# Sheet1_TLK.net
KiCad netlist of a schematic drawn in Altium Designer
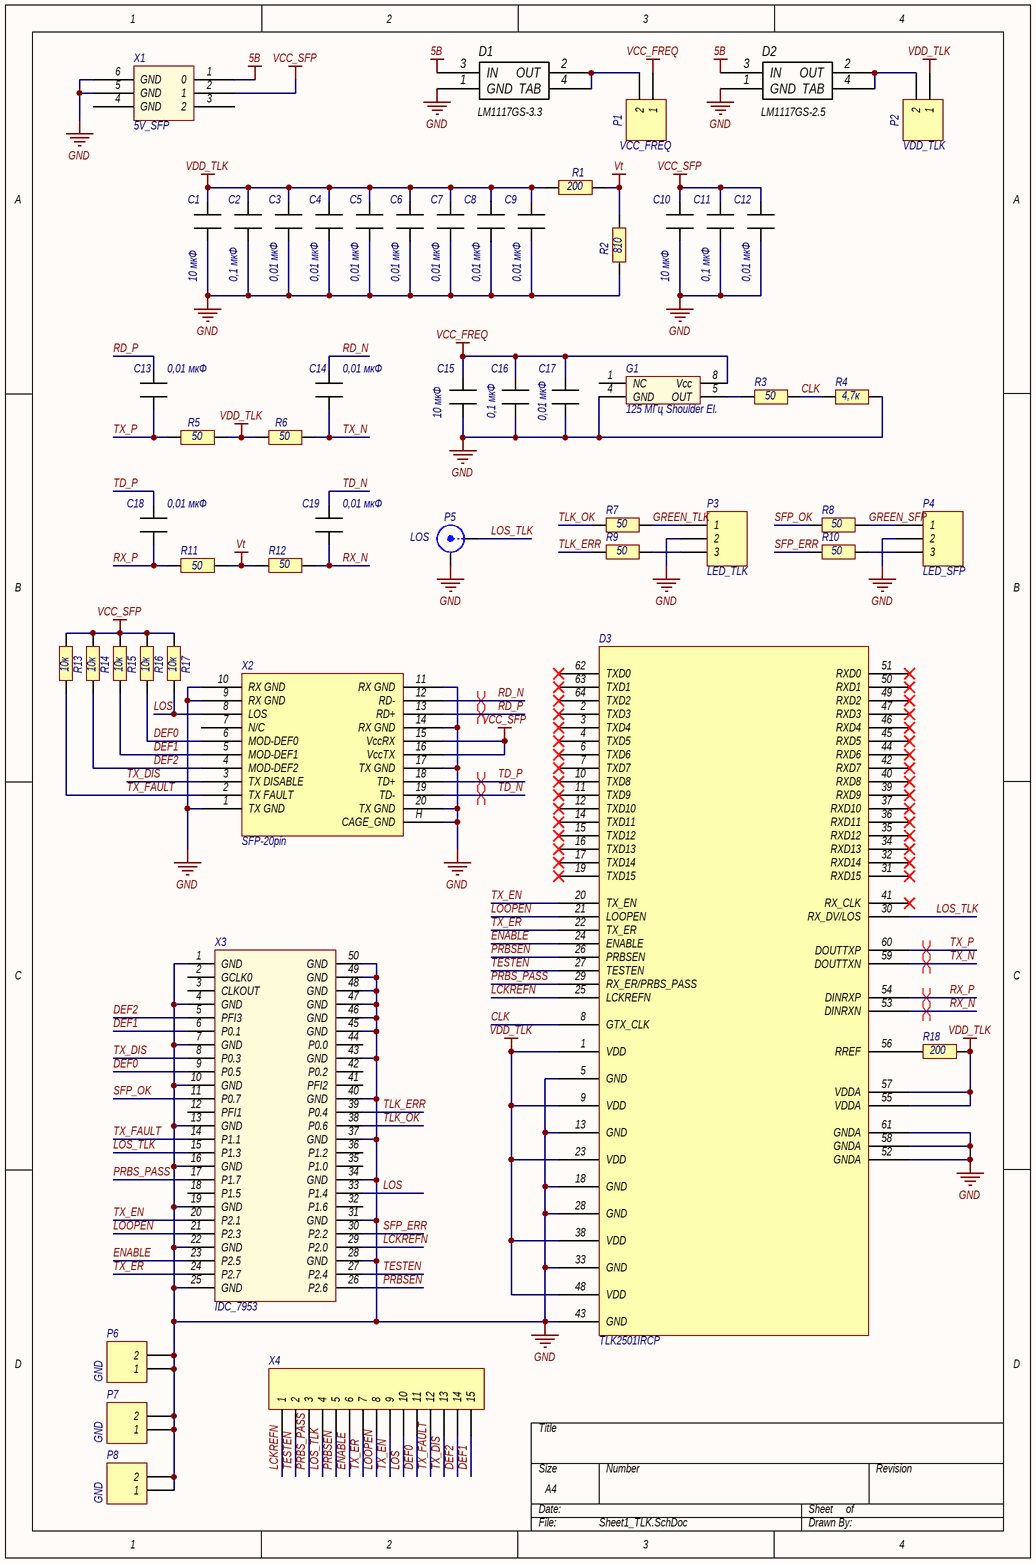
[diagram p0: Sheet1_TLK.SchDoc]

(export (version "E")
  (design (tool "Eeschema 10.0.6"))
  (components
    (comp (ref "C1") (value "10 мкФ") (footprint "Cap_BIG") (libsource (lib "Schlib") (part "CAP_BIG")))
    (comp (ref "C2") (value "0,1 мкФ") (footprint "CAP_SMALL") (libsource (lib "Schlib") (part "CAP_SMALL")))
    (comp (ref "C3") (value "0,01 мкФ") (footprint "CAP_SMALL") (libsource (lib "Schlib") (part "CAP_SMALL")))
    (comp (ref "C4") (value "0,01 мкФ") (footprint "CAP_SMALL") (libsource (lib "Schlib") (part "CAP_SMALL")))
    (comp (ref "C5") (value "0,01 мкФ") (footprint "CAP_SMALL") (libsource (lib "Schlib") (part "CAP_SMALL")))
    (comp (ref "C6") (value "0,01 мкФ") (footprint "CAP_SMALL") (libsource (lib "Schlib") (part "CAP_SMALL")))
    (comp (ref "C7") (value "0,01 мкФ") (footprint "CAP_SMALL") (libsource (lib "Schlib") (part "CAP_SMALL")))
    (comp (ref "C8") (value "0,01 мкФ") (footprint "CAP_SMALL") (libsource (lib "Schlib") (part "CAP_SMALL")))
    (comp (ref "C9") (value "0,01 мкФ") (footprint "CAP_SMALL") (libsource (lib "Schlib") (part "CAP_SMALL")))
    (comp (ref "C10") (value "10 мкФ") (footprint "Cap_BIG") (libsource (lib "Schlib") (part "CAP_BIG")))
    (comp (ref "C11") (value "0,1 мкФ") (footprint "CAP_SMALL") (libsource (lib "Schlib") (part "CAP_SMALL")))
    (comp (ref "C12")
      (value "0,01 мкФ")
      (footprint "CAP_SMALL")
      (libsource (lib "Schlib") (part "CAP_SMALL"))
    )
    (comp (ref "C13")
      (value "0,01 мкФ")
      (footprint "CAP_SMALL")
      (libsource (lib "Schlib") (part "CAP_SMALL"))
    )
    (comp (ref "C14")
      (value "0,01 мкФ")
      (footprint "CAP_SMALL")
      (libsource (lib "Schlib") (part "CAP_SMALL"))
    )
    (comp (ref "C15") (value "10 мкФ") (footprint "Cap_BIG") (libsource (lib "Schlib") (part "CAP_BIG")))
    (comp (ref "C16") (value "0,1 мкФ") (footprint "CAP_SMALL") (libsource (lib "Schlib") (part "CAP_SMALL")))
    (comp (ref "C17")
      (value "0,01 мкФ")
      (footprint "CAP_SMALL")
      (libsource (lib "Schlib") (part "CAP_SMALL"))
    )
    (comp (ref "C18")
      (value "0,01 мкФ")
      (footprint "CAP_SMALL")
      (libsource (lib "Schlib") (part "CAP_SMALL"))
    )
    (comp (ref "C19")
      (value "0,01 мкФ")
      (footprint "CAP_SMALL")
      (libsource (lib "Schlib") (part "CAP_SMALL"))
    )
    (comp (ref "D1")
      (value "LM1117GS-3.3")
      (footprint "LM1117_SOT223")
      (description "Стабилизатор напряжения 3,3В")
      (libsource (lib "VPL") (part "LM1117GS-3.3"))
    )
    (comp (ref "D2")
      (value "LM1117GS-2.5")
      (footprint "LM1117_SOT223")
      (description "Стабилизатор напряжения 2,5В")
      (libsource (lib "VPL") (part "LM1117GS-2.5"))
    )
    (comp (ref "D3")
      (value "TLK2501IRCP")
      (footprint "Quad64")
      (libsource (lib "MIT_Schlib") (part "TLK2501IRCP"))
    )
    (comp (ref "G1")
      (value "125 МГц Shoulder El.")
      (footprint "HALF")
      (libsource (lib "VPL") (part "125 МГц Shoulder El."))
    )
    (comp (ref "P1")
      (value "VCC_FREQ")
      (footprint "HDR1X2")
      (description "Header, 2-Pin")
      (fields (field (name "PUBLISHER") "Altium Limited"))
      (libsource (lib "Miscellaneous Connectors") (part "Header 2"))
    )
    (comp (ref "P2")
      (value "VDD_TLK")
      (footprint "HDR1X2")
      (description "Header, 2-Pin")
      (fields (field (name "PUBLISHER") "Altium Limited"))
      (libsource (lib "Miscellaneous Connectors") (part "Header 2"))
    )
    (comp (ref "P3")
      (value "LED_TLK")
      (footprint "HDR1X3")
      (description "Header, 3-Pin")
      (fields (field (name "PUBLISHER") "Altium Limited"))
      (libsource (lib "Miscellaneous Connectors") (part "Header 3"))
    )
    (comp (ref "P4")
      (value "LED_SFP")
      (footprint "HDR1X3")
      (description "Header, 3-Pin")
      (fields (field (name "PUBLISHER") "Altium Limited"))
      (libsource (lib "Miscellaneous Connectors") (part "Header 3"))
    )
    (comp (ref "P5")
      (value "LOS")
      (footprint "BNC_RA CON")
      (description "BNC Elbow Connector")
      (fields (field (name "PUBLISHER") "Altium Limited"))
      (libsource (lib "Miscellaneous Connectors") (part "BNC"))
    )
    (comp (ref "P6")
      (value "GND")
      (footprint "HDR1X2")
      (description "Header, 2-Pin")
      (fields (field (name "PUBLISHER") "Altium Limited"))
      (libsource (lib "") (part "Header 2_1"))
    )
    (comp (ref "P7")
      (value "GND")
      (footprint "HDR1X2")
      (description "Header, 2-Pin")
      (fields (field (name "PUBLISHER") "Altium Limited"))
      (libsource (lib "") (part "Header 2_1"))
    )
    (comp (ref "P8")
      (value "GND")
      (footprint "HDR1X2")
      (description "Header, 2-Pin")
      (fields (field (name "PUBLISHER") "Altium Limited"))
      (libsource (lib "") (part "Header 2_1"))
    )
    (comp (ref "R1") (value "200") (footprint "RES") (libsource (lib "") (part "RES_2")))
    (comp (ref "R2") (value "810") (footprint "RES") (libsource (lib "") (part "RES_1")))
    (comp (ref "R3") (value "50") (footprint "RES") (libsource (lib "Schlib") (part "RES")))
    (comp (ref "R4") (value "4,7к") (footprint "RES") (libsource (lib "Schlib") (part "RES")))
    (comp (ref "R5") (value "50") (footprint "RES") (libsource (lib "Schlib") (part "RES")))
    (comp (ref "R6") (value "50") (footprint "RES") (libsource (lib "Schlib") (part "RES")))
    (comp (ref "R7") (value "50") (footprint "RES") (libsource (lib "Schlib") (part "RES")))
    (comp (ref "R8") (value "50") (footprint "RES") (libsource (lib "Schlib") (part "RES")))
    (comp (ref "R9") (value "50") (footprint "RES") (libsource (lib "Schlib") (part "RES")))
    (comp (ref "R10") (value "50") (footprint "RES") (libsource (lib "Schlib") (part "RES")))
    (comp (ref "R11") (value "50") (footprint "RES") (libsource (lib "Schlib") (part "RES")))
    (comp (ref "R12") (value "50") (footprint "RES") (libsource (lib "Schlib") (part "RES")))
    (comp (ref "R13") (value "10к") (footprint "RES") (libsource (lib "") (part "RES_1")))
    (comp (ref "R14") (value "10к") (footprint "RES") (libsource (lib "") (part "RES_1")))
    (comp (ref "R15") (value "10к") (footprint "RES") (libsource (lib "") (part "RES_1")))
    (comp (ref "R16") (value "10к") (footprint "RES") (libsource (lib "") (part "RES_1")))
    (comp (ref "R17") (value "10к") (footprint "RES") (libsource (lib "") (part "RES_1")))
    (comp (ref "R18") (value "200") (footprint "RES") (libsource (lib "Schlib") (part "RES")))
    (comp (ref "X1") (value "5V_SFP") (footprint "POWER") (libsource (lib "Schlib") (part "POWER")))
    (comp (ref "X2")
      (value "SFP-20pin")
      (footprint "SFP-20pin")
      (libsource (lib "MIT_Schlib") (part "SFP-20pin"))
    )
    (comp (ref "X3") (value "IDC_7953") (footprint "IDC_7953") (libsource (lib "VPL") (part "IDC_7953")))
    (comp (ref "X4")
      (value "Header 15")
      (footprint "HDR1X15")
      (description "Header, 15-Pin")
      (fields (field (name "PUBLISHER") "Altium Limited"))
      (libsource (lib "Miscellaneous Connectors") (part "Header 15"))
    )
  )
  (nets
    (net (code "1") (name "/CLK") (class "Default")
      (node (ref "D3") (pin "8") (pinfunction "GTX_CLK_8") (pintype "passive"))
      (node (ref "R3") (pin "2") (pinfunction "2_2") (pintype "passive"))
      (node (ref "R4") (pin "1") (pinfunction "1_1") (pintype "passive"))
    )
    (net (code "2") (name "/DEF0") (class "Default")
      (node (ref "R16") (pin "1") (pinfunction "1_1") (pintype "passive"))
      (node (ref "X2") (pin "6") (pinfunction "MOD-DEF0_6") (pintype "passive"))
      (node (ref "X3") (pin "9") (pinfunction "P0.5_9") (pintype "passive"))
      (node (ref "X4") (pin "11") (pinfunction "11_11") (pintype "passive"))
    )
    (net (code "3") (name "/DEF1") (class "Default")
      (node (ref "R15") (pin "1") (pinfunction "1_1") (pintype "passive"))
      (node (ref "X2") (pin "5") (pinfunction "MOD-DEF1_5") (pintype "passive"))
      (node (ref "X3") (pin "6") (pinfunction "P0.1_6") (pintype "passive"))
      (node (ref "X4") (pin "15") (pinfunction "15_15") (pintype "passive"))
    )
    (net (code "4") (name "/DEF2") (class "Default")
      (node (ref "R14") (pin "1") (pinfunction "1_1") (pintype "passive"))
      (node (ref "X2") (pin "4") (pinfunction "MOD-DEF2_4") (pintype "passive"))
      (node (ref "X3") (pin "5") (pinfunction "PFI3_5") (pintype "passive"))
      (node (ref "X4") (pin "14") (pinfunction "14_14") (pintype "passive"))
    )
    (net (code "5") (name "/ENABLE") (class "Default")
      (node (ref "D3") (pin "24") (pinfunction "ENABLE_24") (pintype "passive"))
      (node (ref "X3") (pin "23") (pinfunction "P2.5_23") (pintype "passive"))
      (node (ref "X4") (pin "6") (pinfunction "6_6") (pintype "passive"))
    )
    (net (code "6") (name "/GREEN_SFP") (class "Default")
      (node (ref "P4") (pin "1") (pinfunction "1_1") (pintype "passive"))
      (node (ref "R8") (pin "2") (pinfunction "2_2") (pintype "passive"))
    )
    (net (code "7") (name "/GREEN_TLK") (class "Default")
      (node (ref "P3") (pin "1") (pinfunction "1_1") (pintype "passive"))
      (node (ref "R7") (pin "2") (pinfunction "2_2") (pintype "passive"))
    )
    (net (code "8") (name "/LCKREFN") (class "Default")
      (node (ref "D3") (pin "25") (pinfunction "LCKREFN_25") (pintype "passive"))
      (node (ref "X3") (pin "29") (pinfunction "P2.0_29") (pintype "passive"))
      (node (ref "X4") (pin "1") (pinfunction "1_1") (pintype "passive"))
    )
    (net (code "9") (name "/LOOPEN") (class "Default")
      (node (ref "D3") (pin "21") (pinfunction "LOOPEN_21") (pintype "passive"))
      (node (ref "X3") (pin "21") (pinfunction "P2.3_21") (pintype "passive"))
      (node (ref "X4") (pin "8") (pinfunction "8_8") (pintype "passive"))
    )
    (net (code "10") (name "/LOS") (class "Default")
      (node (ref "R17") (pin "1") (pinfunction "1_1") (pintype "passive"))
      (node (ref "X2") (pin "8") (pinfunction "LOS_8") (pintype "passive"))
      (node (ref "X3") (pin "33") (pinfunction "P1.4_33") (pintype "passive"))
      (node (ref "X4") (pin "10") (pinfunction "10_10") (pintype "passive"))
    )
    (net (code "11") (name "/LOS_TLK") (class "Default")
      (node (ref "D3") (pin "30") (pinfunction "RX_DV/LOS_30") (pintype "passive"))
      (node (ref "P5") (pin "1") (pinfunction "X_1") (pintype "passive"))
      (node (ref "X3") (pin "15") (pinfunction "P1.3_15") (pintype "passive"))
      (node (ref "X4") (pin "4") (pinfunction "4_4") (pintype "passive"))
    )
    (net (code "12") (name "/PRBSEN") (class "Default")
      (node (ref "D3") (pin "26") (pinfunction "PRBSEN_26") (pintype "passive"))
      (node (ref "X3") (pin "26") (pinfunction "P2.6_26") (pintype "passive"))
      (node (ref "X4") (pin "5") (pinfunction "5_5") (pintype "passive"))
    )
    (net (code "13") (name "/PRBS_PASS") (class "Default")
      (node (ref "D3") (pin "29") (pinfunction "RX_ER/PRBS_PASS_29") (pintype "passive"))
      (node (ref "X3") (pin "17") (pinfunction "P1.7_17") (pintype "passive"))
      (node (ref "X4") (pin "3") (pinfunction "3_3") (pintype "passive"))
    )
    (net (code "14") (name "/RD_N") (class "Default")
      (node (ref "C14") (pin "2") (pinfunction "2_2") (pintype "passive"))
      (node (ref "X2") (pin "12") (pinfunction "RD-_12") (pintype "passive"))
    )
    (net (code "15") (name "/RD_P") (class "Default")
      (node (ref "C13") (pin "2") (pinfunction "2_2") (pintype "passive"))
      (node (ref "X2") (pin "13") (pinfunction "RD+_13") (pintype "passive"))
    )
    (net (code "16") (name "/RX_N") (class "Default")
      (node (ref "C19") (pin "1") (pinfunction "1_1") (pintype "passive"))
      (node (ref "D3") (pin "53") (pinfunction "DINRXN_53") (pintype "passive"))
      (node (ref "R12") (pin "2") (pinfunction "2_2") (pintype "passive"))
    )
    (net (code "17") (name "/RX_P") (class "Default")
      (node (ref "C18") (pin "1") (pinfunction "1_1") (pintype "passive"))
      (node (ref "D3") (pin "54") (pinfunction "DINRXP_54") (pintype "passive"))
      (node (ref "R11") (pin "1") (pinfunction "1_1") (pintype "passive"))
    )
    (net (code "18") (name "/SFP_ERR") (class "Default")
      (node (ref "R10") (pin "1") (pinfunction "1_1") (pintype "passive"))
      (node (ref "X3") (pin "30") (pinfunction "P2.2_30") (pintype "passive"))
    )
    (net (code "19") (name "/SFP_OK") (class "Default")
      (node (ref "R8") (pin "1") (pinfunction "1_1") (pintype "passive"))
      (node (ref "X3") (pin "11") (pinfunction "P0.7_11") (pintype "passive"))
    )
    (net (code "20") (name "/TD_N") (class "Default")
      (node (ref "C19") (pin "2") (pinfunction "2_2") (pintype "passive"))
      (node (ref "X2") (pin "19") (pinfunction "TD-_19") (pintype "passive"))
    )
    (net (code "21") (name "/TD_P") (class "Default")
      (node (ref "C18") (pin "2") (pinfunction "2_2") (pintype "passive"))
      (node (ref "X2") (pin "18") (pinfunction "TD+_18") (pintype "passive"))
    )
    (net (code "22") (name "/TESTEN") (class "Default")
      (node (ref "D3") (pin "27") (pinfunction "TESTEN_27") (pintype "passive"))
      (node (ref "X3") (pin "27") (pinfunction "P2.4_27") (pintype "passive"))
      (node (ref "X4") (pin "2") (pinfunction "2_2") (pintype "passive"))
    )
    (net (code "23") (name "/TLK_ERR") (class "Default")
      (node (ref "R9") (pin "1") (pinfunction "1_1") (pintype "passive"))
      (node (ref "X3") (pin "39") (pinfunction "P0.4_39") (pintype "passive"))
    )
    (net (code "24") (name "/TLK_OK") (class "Default")
      (node (ref "R7") (pin "1") (pinfunction "1_1") (pintype "passive"))
      (node (ref "X3") (pin "38") (pinfunction "P0.6_38") (pintype "passive"))
    )
    (net (code "25") (name "/TX_DIS") (class "Default")
      (node (ref "X2") (pin "3") (pinfunction "TX_DISABLE_3") (pintype "passive"))
      (node (ref "X3") (pin "8") (pinfunction "P0.3_8") (pintype "passive"))
      (node (ref "X4") (pin "13") (pinfunction "13_13") (pintype "passive"))
    )
    (net (code "26") (name "/TX_EN") (class "Default")
      (node (ref "D3") (pin "20") (pinfunction "TX_EN_20") (pintype "passive"))
      (node (ref "X3") (pin "20") (pinfunction "P2.1_20") (pintype "passive"))
      (node (ref "X4") (pin "9") (pinfunction "9_9") (pintype "passive"))
    )
    (net (code "27") (name "/TX_ER") (class "Default")
      (node (ref "D3") (pin "22") (pinfunction "TX_ER_22") (pintype "passive"))
      (node (ref "X3") (pin "24") (pinfunction "P2.7_24") (pintype "passive"))
      (node (ref "X4") (pin "7") (pinfunction "7_7") (pintype "passive"))
    )
    (net (code "28") (name "/TX_FAULT") (class "Default")
      (node (ref "R13") (pin "1") (pinfunction "1_1") (pintype "passive"))
      (node (ref "X2") (pin "2") (pinfunction "TX_FAULT_2") (pintype "passive"))
      (node (ref "X3") (pin "14") (pinfunction "P1.1_14") (pintype "passive"))
      (node (ref "X4") (pin "12") (pinfunction "12_12") (pintype "passive"))
    )
    (net (code "29") (name "/TX_N") (class "Default")
      (node (ref "C14") (pin "1") (pinfunction "1_1") (pintype "passive"))
      (node (ref "D3") (pin "59") (pinfunction "DOUTTXN_59") (pintype "passive"))
      (node (ref "R6") (pin "2") (pinfunction "2_2") (pintype "passive"))
    )
    (net (code "30") (name "/TX_P") (class "Default")
      (node (ref "C13") (pin "1") (pinfunction "1_1") (pintype "passive"))
      (node (ref "D3") (pin "60") (pinfunction "DOUTTXP_60") (pintype "passive"))
      (node (ref "R5") (pin "1") (pinfunction "1_1") (pintype "passive"))
    )
    (net (code "31") (name "5В") (class "Default")
      (node (ref "D1") (pin "3") (pinfunction "IN_3") (pintype "power_in"))
      (node (ref "D2") (pin "3") (pinfunction "IN_3") (pintype "power_in"))
      (node (ref "X1") (pin "1") (pinfunction "0_1") (pintype "passive"))
    )
    (net (code "32") (name "GND") (class "Default")
      (node (ref "C1") (pin "1") (pinfunction "1_1") (pintype "passive"))
      (node (ref "C10") (pin "1") (pinfunction "1_1") (pintype "passive"))
      (node (ref "C11") (pin "1") (pinfunction "1_1") (pintype "passive"))
      (node (ref "C12") (pin "1") (pinfunction "1_1") (pintype "passive"))
      (node (ref "C15") (pin "1") (pinfunction "1_1") (pintype "passive"))
      (node (ref "C16") (pin "1") (pinfunction "1_1") (pintype "passive"))
      (node (ref "C17") (pin "1") (pinfunction "1_1") (pintype "passive"))
      (node (ref "C2") (pin "1") (pinfunction "1_1") (pintype "passive"))
      (node (ref "C3") (pin "1") (pinfunction "1_1") (pintype "passive"))
      (node (ref "C4") (pin "1") (pinfunction "1_1") (pintype "passive"))
      (node (ref "C5") (pin "1") (pinfunction "1_1") (pintype "passive"))
      (node (ref "C6") (pin "1") (pinfunction "1_1") (pintype "passive"))
      (node (ref "C7") (pin "1") (pinfunction "1_1") (pintype "passive"))
      (node (ref "C8") (pin "1") (pinfunction "1_1") (pintype "passive"))
      (node (ref "C9") (pin "1") (pinfunction "1_1") (pintype "passive"))
      (node (ref "D1") (pin "1") (pinfunction "GND_1") (pintype "passive"))
      (node (ref "D2") (pin "1") (pinfunction "GND_1") (pintype "passive"))
      (node (ref "D3") (pin "13") (pinfunction "GND_13") (pintype "passive"))
      (node (ref "D3") (pin "18") (pinfunction "GND_18") (pintype "passive"))
      (node (ref "D3") (pin "28") (pinfunction "GND_28") (pintype "passive"))
      (node (ref "D3") (pin "33") (pinfunction "GND_33") (pintype "passive"))
      (node (ref "D3") (pin "43") (pinfunction "GND_43") (pintype "passive"))
      (node (ref "D3") (pin "5") (pinfunction "GND_5") (pintype "passive"))
      (node (ref "D3") (pin "52") (pinfunction "GNDA_52") (pintype "passive"))
      (node (ref "D3") (pin "58") (pinfunction "GNDA_58") (pintype "passive"))
      (node (ref "D3") (pin "61") (pinfunction "GNDA_61") (pintype "passive"))
      (node (ref "G1") (pin "4") (pinfunction "GND_4") (pintype "passive"))
      (node (ref "P3") (pin "2") (pinfunction "2_2") (pintype "passive"))
      (node (ref "P4") (pin "2") (pinfunction "2_2") (pintype "passive"))
      (node (ref "P5") (pin "2") (pinfunction "Y_2") (pintype "passive"))
      (node (ref "P6") (pin "1") (pinfunction "1_1") (pintype "passive"))
      (node (ref "P6") (pin "2") (pinfunction "2_2") (pintype "passive"))
      (node (ref "P7") (pin "1") (pinfunction "1_1") (pintype "passive"))
      (node (ref "P7") (pin "2") (pinfunction "2_2") (pintype "passive"))
      (node (ref "P8") (pin "1") (pinfunction "1_1") (pintype "passive"))
      (node (ref "P8") (pin "2") (pinfunction "2_2") (pintype "passive"))
      (node (ref "R2") (pin "1") (pinfunction "1_1") (pintype "passive"))
      (node (ref "R4") (pin "2") (pinfunction "2_2") (pintype "passive"))
      (node (ref "X1") (pin "5") (pinfunction "GND_5") (pintype "passive"))
      (node (ref "X1") (pin "6") (pinfunction "GND_6") (pintype "passive"))
      (node (ref "X2") (pin "1") (pinfunction "TX_GND_1") (pintype "passive"))
      (node (ref "X2") (pin "10") (pinfunction "RX_GND_10") (pintype "passive"))
      (node (ref "X2") (pin "11") (pinfunction "RX_GND_11") (pintype "passive"))
      (node (ref "X2") (pin "14") (pinfunction "RX_GND_14") (pintype "passive"))
      (node (ref "X2") (pin "17") (pinfunction "TX_GND_17") (pintype "passive"))
      (node (ref "X2") (pin "20") (pinfunction "TX_GND_20") (pintype "passive"))
      (node (ref "X2") (pin "9") (pinfunction "RX_GND_9") (pintype "passive"))
      (node (ref "X2") (pin "H") (pinfunction "CAGE_GND_H") (pintype "passive"))
      (node (ref "X3") (pin "1") (pinfunction "GND_1") (pintype "passive"))
      (node (ref "X3") (pin "10") (pinfunction "GND_10") (pintype "passive"))
      (node (ref "X3") (pin "13") (pinfunction "GND_13") (pintype "passive"))
      (node (ref "X3") (pin "16") (pinfunction "GND_16") (pintype "passive"))
      (node (ref "X3") (pin "19") (pinfunction "GND_19") (pintype "passive"))
      (node (ref "X3") (pin "22") (pinfunction "GND_22") (pintype "passive"))
      (node (ref "X3") (pin "25") (pinfunction "GND_25") (pintype "passive"))
      (node (ref "X3") (pin "28") (pinfunction "GND_28") (pintype "passive"))
      (node (ref "X3") (pin "31") (pinfunction "GND_31") (pintype "passive"))
      (node (ref "X3") (pin "34") (pinfunction "GND_34") (pintype "passive"))
      (node (ref "X3") (pin "37") (pinfunction "GND_37") (pintype "passive"))
      (node (ref "X3") (pin "4") (pinfunction "GND_4") (pintype "passive"))
      (node (ref "X3") (pin "40") (pinfunction "GND_40") (pintype "passive"))
      (node (ref "X3") (pin "43") (pinfunction "GND_43") (pintype "passive"))
      (node (ref "X3") (pin "45") (pinfunction "GND_45") (pintype "passive"))
      (node (ref "X3") (pin "46") (pinfunction "GND_46") (pintype "passive"))
      (node (ref "X3") (pin "47") (pinfunction "GND_47") (pintype "passive"))
      (node (ref "X3") (pin "48") (pinfunction "GND_48") (pintype "passive"))
      (node (ref "X3") (pin "49") (pinfunction "GND_49") (pintype "passive"))
      (node (ref "X3") (pin "50") (pinfunction "GND_50") (pintype "passive"))
      (node (ref "X3") (pin "7") (pinfunction "GND_7") (pintype "passive"))
    )
    (net (code "33") (name "Net-(D1-OUT)") (class "Default")
      (node (ref "D1") (pin "2") (pinfunction "OUT_2") (pintype "passive"))
      (node (ref "D1") (pin "4") (pinfunction "TAB_4") (pintype "passive"))
      (node (ref "P1") (pin "2") (pinfunction "2_2") (pintype "passive"))
    )
    (net (code "34") (name "Net-(D2-OUT)") (class "Default")
      (node (ref "D2") (pin "2") (pinfunction "OUT_2") (pintype "passive"))
      (node (ref "D2") (pin "4") (pinfunction "TAB_4") (pintype "passive"))
      (node (ref "P2") (pin "2") (pinfunction "2_2") (pintype "passive"))
    )
    (net (code "35") (name "Net-(D3-RREF)") (class "Default")
      (node (ref "D3") (pin "56") (pinfunction "RREF_56") (pintype "passive"))
      (node (ref "R18") (pin "1") (pinfunction "1_1") (pintype "passive"))
    )
    (net (code "36") (name "Net-(G1-OUT)") (class "Default")
      (node (ref "G1") (pin "5") (pinfunction "OUT_5") (pintype "passive"))
      (node (ref "R3") (pin "1") (pinfunction "1_1") (pintype "passive"))
    )
    (net (code "37") (name "Net-(P3-Pad3)") (class "Default")
      (node (ref "P3") (pin "3") (pinfunction "3_3") (pintype "passive"))
      (node (ref "R9") (pin "2") (pinfunction "2_2") (pintype "passive"))
    )
    (net (code "38") (name "Net-(P4-Pad3)") (class "Default")
      (node (ref "P4") (pin "3") (pinfunction "3_3") (pintype "passive"))
      (node (ref "R10") (pin "2") (pinfunction "2_2") (pintype "passive"))
    )
    (net (code "39") (name "VCC_FREQ") (class "Default")
      (node (ref "C15") (pin "2") (pinfunction "2_2") (pintype "passive"))
      (node (ref "C16") (pin "2") (pinfunction "2_2") (pintype "passive"))
      (node (ref "C17") (pin "2") (pinfunction "2_2") (pintype "passive"))
      (node (ref "G1") (pin "8") (pinfunction "Vcc_8") (pintype "passive"))
      (node (ref "P1") (pin "1") (pinfunction "1_1") (pintype "passive"))
    )
    (net (code "40") (name "VCC_SFP") (class "Default")
      (node (ref "C10") (pin "2") (pinfunction "2_2") (pintype "passive"))
      (node (ref "C11") (pin "2") (pinfunction "2_2") (pintype "passive"))
      (node (ref "C12") (pin "2") (pinfunction "2_2") (pintype "passive"))
      (node (ref "R13") (pin "2") (pinfunction "2_2") (pintype "passive"))
      (node (ref "R14") (pin "2") (pinfunction "2_2") (pintype "passive"))
      (node (ref "R15") (pin "2") (pinfunction "2_2") (pintype "passive"))
      (node (ref "R16") (pin "2") (pinfunction "2_2") (pintype "passive"))
      (node (ref "R17") (pin "2") (pinfunction "2_2") (pintype "passive"))
      (node (ref "X1") (pin "2") (pinfunction "1_2") (pintype "passive"))
      (node (ref "X2") (pin "15") (pinfunction "VccRX_15") (pintype "passive"))
      (node (ref "X2") (pin "16") (pinfunction "VccTX_16") (pintype "passive"))
    )
    (net (code "41") (name "VDD_TLK") (class "Default")
      (node (ref "C1") (pin "2") (pinfunction "2_2") (pintype "passive"))
      (node (ref "C2") (pin "2") (pinfunction "2_2") (pintype "passive"))
      (node (ref "C3") (pin "2") (pinfunction "2_2") (pintype "passive"))
      (node (ref "C4") (pin "2") (pinfunction "2_2") (pintype "passive"))
      (node (ref "C5") (pin "2") (pinfunction "2_2") (pintype "passive"))
      (node (ref "C6") (pin "2") (pinfunction "2_2") (pintype "passive"))
      (node (ref "C7") (pin "2") (pinfunction "2_2") (pintype "passive"))
      (node (ref "C8") (pin "2") (pinfunction "2_2") (pintype "passive"))
      (node (ref "C9") (pin "2") (pinfunction "2_2") (pintype "passive"))
      (node (ref "D3") (pin "1") (pinfunction "VDD_1") (pintype "passive"))
      (node (ref "D3") (pin "23") (pinfunction "VDD_23") (pintype "passive"))
      (node (ref "D3") (pin "38") (pinfunction "VDD_38") (pintype "passive"))
      (node (ref "D3") (pin "48") (pinfunction "VDD_48") (pintype "passive"))
      (node (ref "D3") (pin "55") (pinfunction "VDDA_55") (pintype "passive"))
      (node (ref "D3") (pin "57") (pinfunction "VDDA_57") (pintype "passive"))
      (node (ref "D3") (pin "9") (pinfunction "VDD_9") (pintype "passive"))
      (node (ref "P2") (pin "1") (pinfunction "1_1") (pintype "passive"))
      (node (ref "R1") (pin "2") (pinfunction "2_2") (pintype "passive"))
      (node (ref "R18") (pin "2") (pinfunction "2_2") (pintype "passive"))
      (node (ref "R5") (pin "2") (pinfunction "2_2") (pintype "passive"))
      (node (ref "R6") (pin "1") (pinfunction "1_1") (pintype "passive"))
    )
    (net (code "42") (name "Vt") (class "Default")
      (node (ref "R1") (pin "1") (pinfunction "1_1") (pintype "passive"))
      (node (ref "R11") (pin "2") (pinfunction "2_2") (pintype "passive"))
      (node (ref "R12") (pin "1") (pinfunction "1_1") (pintype "passive"))
      (node (ref "R2") (pin "2") (pinfunction "2_2") (pintype "passive"))
    )
    (net (code "43") (name "unconnected-(D3-RXD0-Pad51)") (class "Default")
      (node (ref "D3") (pin "51") (pinfunction "RXD0_51") (pintype "passive+no_connect"))
    )
    (net (code "44") (name "unconnected-(D3-RXD1-Pad50)") (class "Default")
      (node (ref "D3") (pin "50") (pinfunction "RXD1_50") (pintype "passive+no_connect"))
    )
    (net (code "45") (name "unconnected-(D3-RXD2-Pad49)") (class "Default")
      (node (ref "D3") (pin "49") (pinfunction "RXD2_49") (pintype "passive+no_connect"))
    )
    (net (code "46") (name "unconnected-(D3-RXD3-Pad47)") (class "Default")
      (node (ref "D3") (pin "47") (pinfunction "RXD3_47") (pintype "passive+no_connect"))
    )
    (net (code "47") (name "unconnected-(D3-RXD4-Pad46)") (class "Default")
      (node (ref "D3") (pin "46") (pinfunction "RXD4_46") (pintype "passive+no_connect"))
    )
    (net (code "48") (name "unconnected-(D3-RXD5-Pad45)") (class "Default")
      (node (ref "D3") (pin "45") (pinfunction "RXD5_45") (pintype "passive+no_connect"))
    )
    (net (code "49") (name "unconnected-(D3-RXD6-Pad44)") (class "Default")
      (node (ref "D3") (pin "44") (pinfunction "RXD6_44") (pintype "passive+no_connect"))
    )
    (net (code "50") (name "unconnected-(D3-RXD7-Pad42)") (class "Default")
      (node (ref "D3") (pin "42") (pinfunction "RXD7_42") (pintype "passive+no_connect"))
    )
    (net (code "51") (name "unconnected-(D3-RXD8-Pad40)") (class "Default")
      (node (ref "D3") (pin "40") (pinfunction "RXD8_40") (pintype "passive+no_connect"))
    )
    (net (code "52") (name "unconnected-(D3-RXD9-Pad39)") (class "Default")
      (node (ref "D3") (pin "39") (pinfunction "RXD9_39") (pintype "passive+no_connect"))
    )
    (net (code "53") (name "unconnected-(D3-RXD10-Pad37)") (class "Default")
      (node (ref "D3") (pin "37") (pinfunction "RXD10_37") (pintype "passive+no_connect"))
    )
    (net (code "54") (name "unconnected-(D3-RXD11-Pad36)") (class "Default")
      (node (ref "D3") (pin "36") (pinfunction "RXD11_36") (pintype "passive+no_connect"))
    )
    (net (code "55") (name "unconnected-(D3-RXD12-Pad35)") (class "Default")
      (node (ref "D3") (pin "35") (pinfunction "RXD12_35") (pintype "passive+no_connect"))
    )
    (net (code "56") (name "unconnected-(D3-RXD13-Pad34)") (class "Default")
      (node (ref "D3") (pin "34") (pinfunction "RXD13_34") (pintype "passive+no_connect"))
    )
    (net (code "57") (name "unconnected-(D3-RXD14-Pad32)") (class "Default")
      (node (ref "D3") (pin "32") (pinfunction "RXD14_32") (pintype "passive+no_connect"))
    )
    (net (code "58") (name "unconnected-(D3-RXD15-Pad31)") (class "Default")
      (node (ref "D3") (pin "31") (pinfunction "RXD15_31") (pintype "passive+no_connect"))
    )
    (net (code "59") (name "unconnected-(D3-RX_CLK-Pad41)") (class "Default")
      (node (ref "D3") (pin "41") (pinfunction "RX_CLK_41") (pintype "passive+no_connect"))
    )
    (net (code "60") (name "unconnected-(D3-TXD0-Pad62)") (class "Default")
      (node (ref "D3") (pin "62") (pinfunction "TXD0_62") (pintype "passive+no_connect"))
    )
    (net (code "61") (name "unconnected-(D3-TXD1-Pad63)") (class "Default")
      (node (ref "D3") (pin "63") (pinfunction "TXD1_63") (pintype "passive+no_connect"))
    )
    (net (code "62") (name "unconnected-(D3-TXD2-Pad64)") (class "Default")
      (node (ref "D3") (pin "64") (pinfunction "TXD2_64") (pintype "passive+no_connect"))
    )
    (net (code "63") (name "unconnected-(D3-TXD3-Pad2)") (class "Default")
      (node (ref "D3") (pin "2") (pinfunction "TXD3_2") (pintype "passive+no_connect"))
    )
    (net (code "64") (name "unconnected-(D3-TXD4-Pad3)") (class "Default")
      (node (ref "D3") (pin "3") (pinfunction "TXD4_3") (pintype "passive+no_connect"))
    )
    (net (code "65") (name "unconnected-(D3-TXD5-Pad4)") (class "Default")
      (node (ref "D3") (pin "4") (pinfunction "TXD5_4") (pintype "passive+no_connect"))
    )
    (net (code "66") (name "unconnected-(D3-TXD6-Pad6)") (class "Default")
      (node (ref "D3") (pin "6") (pinfunction "TXD6_6") (pintype "passive+no_connect"))
    )
    (net (code "67") (name "unconnected-(D3-TXD7-Pad7)") (class "Default")
      (node (ref "D3") (pin "7") (pinfunction "TXD7_7") (pintype "passive+no_connect"))
    )
    (net (code "68") (name "unconnected-(D3-TXD8-Pad10)") (class "Default")
      (node (ref "D3") (pin "10") (pinfunction "TXD8_10") (pintype "passive+no_connect"))
    )
    (net (code "69") (name "unconnected-(D3-TXD9-Pad11)") (class "Default")
      (node (ref "D3") (pin "11") (pinfunction "TXD9_11") (pintype "passive+no_connect"))
    )
    (net (code "70") (name "unconnected-(D3-TXD10-Pad12)") (class "Default")
      (node (ref "D3") (pin "12") (pinfunction "TXD10_12") (pintype "passive+no_connect"))
    )
    (net (code "71") (name "unconnected-(D3-TXD11-Pad14)") (class "Default")
      (node (ref "D3") (pin "14") (pinfunction "TXD11_14") (pintype "passive+no_connect"))
    )
    (net (code "72") (name "unconnected-(D3-TXD12-Pad15)") (class "Default")
      (node (ref "D3") (pin "15") (pinfunction "TXD12_15") (pintype "passive+no_connect"))
    )
    (net (code "73") (name "unconnected-(D3-TXD13-Pad16)") (class "Default")
      (node (ref "D3") (pin "16") (pinfunction "TXD13_16") (pintype "passive+no_connect"))
    )
    (net (code "74") (name "unconnected-(D3-TXD14-Pad17)") (class "Default")
      (node (ref "D3") (pin "17") (pinfunction "TXD14_17") (pintype "passive+no_connect"))
    )
    (net (code "75") (name "unconnected-(D3-TXD15-Pad19)") (class "Default")
      (node (ref "D3") (pin "19") (pinfunction "TXD15_19") (pintype "passive+no_connect"))
    )
    (net (code "76") (name "unconnected-(G1-NC-Pad1)") (class "Default")
      (node (ref "G1") (pin "1") (pinfunction "NC_1") (pintype "passive"))
    )
    (net (code "77") (name "unconnected-(X1-2-Pad3)") (class "Default")
      (node (ref "X1") (pin "3") (pinfunction "2_3") (pintype "passive"))
    )
    (net (code "78") (name "unconnected-(X1-GND-Pad4)") (class "Default")
      (node (ref "X1") (pin "4") (pinfunction "GND_4") (pintype "passive"))
    )
    (net (code "79") (name "unconnected-(X2-N{slash}C-Pad7)") (class "Default")
      (node (ref "X2") (pin "7") (pinfunction "N/C_7") (pintype "passive"))
    )
    (net (code "80") (name "unconnected-(X3-CLKOUT-Pad3)") (class "Default")
      (node (ref "X3") (pin "3") (pinfunction "CLKOUT_3") (pintype "passive"))
    )
    (net (code "81") (name "unconnected-(X3-GCLK0-Pad2)") (class "Default")
      (node (ref "X3") (pin "2") (pinfunction "GCLK0_2") (pintype "passive"))
    )
    (net (code "82") (name "unconnected-(X3-P0.0-Pad44)") (class "Default")
      (node (ref "X3") (pin "44") (pinfunction "P0.0_44") (pintype "passive"))
    )
    (net (code "83") (name "unconnected-(X3-P0.2-Pad42)") (class "Default")
      (node (ref "X3") (pin "42") (pinfunction "P0.2_42") (pintype "passive"))
    )
    (net (code "84") (name "unconnected-(X3-P1.0-Pad35)") (class "Default")
      (node (ref "X3") (pin "35") (pinfunction "P1.0_35") (pintype "passive"))
    )
    (net (code "85") (name "unconnected-(X3-P1.2-Pad36)") (class "Default")
      (node (ref "X3") (pin "36") (pinfunction "P1.2_36") (pintype "passive"))
    )
    (net (code "86") (name "unconnected-(X3-P1.5-Pad18)") (class "Default")
      (node (ref "X3") (pin "18") (pinfunction "P1.5_18") (pintype "passive"))
    )
    (net (code "87") (name "unconnected-(X3-P1.6-Pad32)") (class "Default")
      (node (ref "X3") (pin "32") (pinfunction "P1.6_32") (pintype "passive"))
    )
    (net (code "88") (name "unconnected-(X3-PFI1-Pad12)") (class "Default")
      (node (ref "X3") (pin "12") (pinfunction "PFI1_12") (pintype "passive"))
    )
    (net (code "89") (name "unconnected-(X3-PFI2-Pad41)") (class "Default")
      (node (ref "X3") (pin "41") (pinfunction "PFI2_41") (pintype "passive"))
    )
  )
)
